# SCH_Driver_RL.net
KiCad netlist of a schematic drawn in Altium Designer
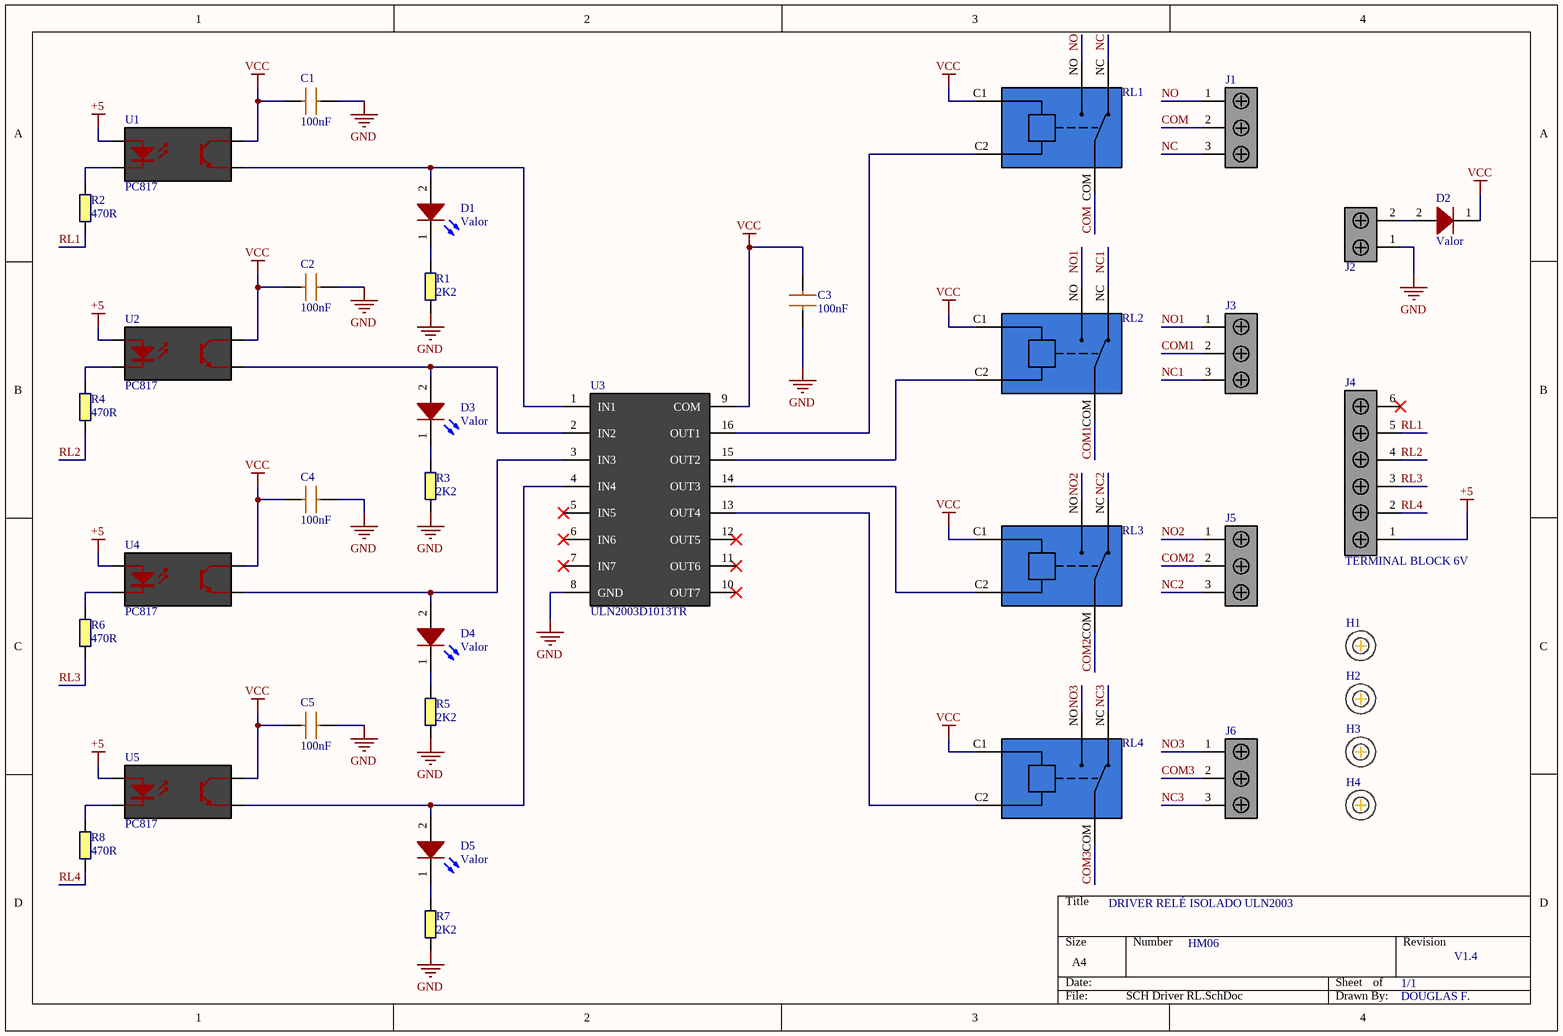
[diagram p0: SCH Driver RL.SchDoc]

(export (version "E")
  (design (tool "Eeschema 10.0.6"))
  (components
    (comp (ref "C1")
      (value "100nF")
      (footprint "RAD-0.2")
      (description "Capacitor")
      (fields (field (name "PUBLISHER") "Altium Limited"))
      (libsource (lib "Driver relé") (part "CAPACITOR"))
    )
    (comp (ref "C2")
      (value "100nF")
      (footprint "RAD-0.2")
      (description "Capacitor")
      (fields (field (name "PUBLISHER") "Altium Limited"))
      (libsource (lib "Driver relé") (part "CAPACITOR"))
    )
    (comp (ref "C3")
      (value "100nF")
      (footprint "RAD-0.2")
      (description "Capacitor")
      (fields (field (name "PUBLISHER") "Altium Limited"))
      (libsource (lib "Driver relé") (part "CAPACITOR"))
    )
    (comp (ref "C4")
      (value "100nF")
      (footprint "RAD-0.2")
      (description "Capacitor")
      (fields (field (name "PUBLISHER") "Altium Limited"))
      (libsource (lib "Driver relé") (part "CAPACITOR"))
    )
    (comp (ref "C5")
      (value "100nF")
      (footprint "RAD-0.2")
      (description "Capacitor")
      (fields (field (name "PUBLISHER") "Altium Limited"))
      (libsource (lib "Driver relé") (part "CAPACITOR"))
    )
    (comp (ref "D1")
      (value "Valor")
      (footprint "LED 3MM")
      (description "Typical RED, GREEN, YELLOW, AMBER GaAs LED")
      (fields (field (name "PUBLISHER") "Altium Limited"))
      (libsource (lib "Driver relé") (part "LED"))
    )
    (comp (ref "D2")
      (value "Valor")
      (footprint "1N4007 DO-41")
      (description "Diodo rapido")
      (fields (field (name "PUBLISHER") "Altium Limited"))
      (libsource (lib "Driver relé") (part "DIODO 1N4007"))
    )
    (comp (ref "D3")
      (value "Valor")
      (footprint "LED 3MM")
      (description "Typical RED, GREEN, YELLOW, AMBER GaAs LED")
      (fields (field (name "PUBLISHER") "Altium Limited"))
      (libsource (lib "Driver relé") (part "LED"))
    )
    (comp (ref "D4")
      (value "Valor")
      (footprint "LED 3MM")
      (description "Typical RED, GREEN, YELLOW, AMBER GaAs LED")
      (fields (field (name "PUBLISHER") "Altium Limited"))
      (libsource (lib "Driver relé") (part "LED"))
    )
    (comp (ref "D5")
      (value "Valor")
      (footprint "LED 3MM")
      (description "Typical RED, GREEN, YELLOW, AMBER GaAs LED")
      (fields (field (name "PUBLISHER") "Altium Limited"))
      (libsource (lib "Driver relé") (part "LED"))
    )
    (comp (ref "H1") (value "M3") (footprint "Parafuso M3") (libsource (lib "Driver relé") (part "Furo M3")))
    (comp (ref "H2") (value "M3") (footprint "Parafuso M3") (libsource (lib "Driver relé") (part "Furo M3")))
    (comp (ref "H3") (value "M3") (footprint "Parafuso M3") (libsource (lib "Driver relé") (part "Furo M3")))
    (comp (ref "H4") (value "M3") (footprint "Parafuso M3") (libsource (lib "Driver relé") (part "Furo M3")))
    (comp (ref "J1")
      (value "Conector 2v Phoenix")
      (footprint "Terminal block 5mm 3V")
      (description "Block, Terminal; 6 A; 63 V; 5 mm; 26 to 20 AWG; 3; Screw; Soldering; 1.5 kV")
      (fields
        (field (name "MANUFACTURER") "Phoenix Contact")
        (field (name "MANUFACTURER PART NUMBER") "1725656")
      )
      (libsource (lib "Driver relé") (part "TERMINAL BLOCK 3V"))
    )
    (comp (ref "J2")
      (value "Conector 2v Phoenix")
      (footprint "Terminal block 5mm 2V")
      (description "Block, Terminal; 6 A; 63 V; 5 mm; 26 to 20 AWG; 2; Screw; Soldering; 1.5 kV")
      (fields
        (field (name "MANUFACTURER") "Phoenix Contact")
        (field (name "MANUFACTURER PART NUMBER") "1725656")
      )
      (libsource (lib "Driver relé") (part "TERMINAL BLOCK 2V"))
    )
    (comp (ref "J3")
      (value "Conector 2v Phoenix")
      (footprint "Terminal block 5mm 3V")
      (description "Block, Terminal; 6 A; 63 V; 5 mm; 26 to 20 AWG; 3; Screw; Soldering; 1.5 kV")
      (fields
        (field (name "MANUFACTURER") "Phoenix Contact")
        (field (name "MANUFACTURER PART NUMBER") "1725656")
      )
      (libsource (lib "Driver relé") (part "TERMINAL BLOCK 3V"))
    )
    (comp (ref "J4")
      (value "TERMINAL BLOCK 6V")
      (footprint "Terminal block 5mm 6V")
      (description "Block, Terminal; 6 A; 63 V; 5 mm; 26 to 20 AWG; 6 Screw; Soldering; 1.5 kV")
      (libsource (lib "Driver relé") (part "TERMINAL BLOCK 6V"))
    )
    (comp (ref "J5")
      (value "Conector 2v Phoenix")
      (footprint "Terminal block 5mm 3V")
      (description "Block, Terminal; 6 A; 63 V; 5 mm; 26 to 20 AWG; 3; Screw; Soldering; 1.5 kV")
      (fields
        (field (name "MANUFACTURER") "Phoenix Contact")
        (field (name "MANUFACTURER PART NUMBER") "1725656")
      )
      (libsource (lib "Driver relé") (part "TERMINAL BLOCK 3V"))
    )
    (comp (ref "J6")
      (value "Conector 2v Phoenix")
      (footprint "Terminal block 5mm 3V")
      (description "Block, Terminal; 6 A; 63 V; 5 mm; 26 to 20 AWG; 3; Screw; Soldering; 1.5 kV")
      (fields
        (field (name "MANUFACTURER") "Phoenix Contact")
        (field (name "MANUFACTURER PART NUMBER") "1725656")
      )
      (libsource (lib "Driver relé") (part "TERMINAL BLOCK 3V"))
    )
    (comp (ref "R1")
      (value "2K2")
      (footprint "RES 1/4 PTH")
      (description "Resistor")
      (fields (field (name "PUBLISHER") "Altium Limited"))
      (libsource (lib "") (part "RESISTOR 1/4W_1"))
    )
    (comp (ref "R2")
      (value "470R")
      (footprint "RES 1/4 PTH")
      (description "Resistor")
      (fields (field (name "PUBLISHER") "Altium Limited"))
      (libsource (lib "Driver relé") (part "RESISTOR 1/4W"))
    )
    (comp (ref "R3")
      (value "2K2")
      (footprint "RES 1/4 PTH")
      (description "Resistor")
      (fields (field (name "PUBLISHER") "Altium Limited"))
      (libsource (lib "") (part "RESISTOR 1/4W_1"))
    )
    (comp (ref "R4")
      (value "470R")
      (footprint "RES 1/4 PTH")
      (description "Resistor")
      (fields (field (name "PUBLISHER") "Altium Limited"))
      (libsource (lib "Driver relé") (part "RESISTOR 1/4W"))
    )
    (comp (ref "R5")
      (value "2K2")
      (footprint "RES 1/4 PTH")
      (description "Resistor")
      (fields (field (name "PUBLISHER") "Altium Limited"))
      (libsource (lib "") (part "RESISTOR 1/4W_1"))
    )
    (comp (ref "R6")
      (value "470R")
      (footprint "RES 1/4 PTH")
      (description "Resistor")
      (fields (field (name "PUBLISHER") "Altium Limited"))
      (libsource (lib "Driver relé") (part "RESISTOR 1/4W"))
    )
    (comp (ref "R7")
      (value "2K2")
      (footprint "RES 1/4 PTH")
      (description "Resistor")
      (fields (field (name "PUBLISHER") "Altium Limited"))
      (libsource (lib "") (part "RESISTOR 1/4W_1"))
    )
    (comp (ref "R8")
      (value "470R")
      (footprint "RES 1/4 PTH")
      (description "Resistor")
      (fields (field (name "PUBLISHER") "Altium Limited"))
      (libsource (lib "Driver relé") (part "RESISTOR 1/4W"))
    )
    (comp (ref "RL1")
      (value "Relé 12v 5p")
      (footprint "RELAY")
      (libsource (lib "Driver relé") (part "Relé 12v 5p"))
    )
    (comp (ref "RL2")
      (value "Relé 12v 5p")
      (footprint "RELAY")
      (libsource (lib "Driver relé") (part "Relé 12v 5p"))
    )
    (comp (ref "RL3")
      (value "Relé 12v 5p")
      (footprint "RELAY")
      (libsource (lib "Driver relé") (part "Relé 12v 5p"))
    )
    (comp (ref "RL4")
      (value "Relé 12v 5p")
      (footprint "RELAY")
      (libsource (lib "Driver relé") (part "Relé 12v 5p"))
    )
    (comp (ref "U1") (value "PC817") (footprint "PC817 DIP-4") (libsource (lib "Driver relé") (part "PC817")))
    (comp (ref "U2") (value "PC817") (footprint "PC817 DIP-4") (libsource (lib "Driver relé") (part "PC817")))
    (comp (ref "U3")
      (value "ULN2003D1013TR")
      (footprint "PDIP-16")
      (description "ULN Series 50V 500 mA High Voltage High Current Seven Darlington Array - SOIC-16")
      (fields (field (name "MANUFACTURER") "STMicroelectronics"))
      (libsource (lib "Driver relé") (part "ULN2003D1013TR"))
    )
    (comp (ref "U4") (value "PC817") (footprint "PC817 DIP-4") (libsource (lib "Driver relé") (part "PC817")))
    (comp (ref "U5") (value "PC817") (footprint "PC817 DIP-4") (libsource (lib "Driver relé") (part "PC817")))
  )
  (nets
    (net (code "1") (name "+5") (class "Default")
      (node (ref "J4") (pin "1") (pinfunction "1_1") (pintype "passive"))
      (node (ref "U1") (pin "1") (pinfunction "A_1") (pintype "passive"))
      (node (ref "U2") (pin "1") (pinfunction "A_1") (pintype "passive"))
      (node (ref "U4") (pin "1") (pinfunction "A_1") (pintype "passive"))
      (node (ref "U5") (pin "1") (pinfunction "A_1") (pintype "passive"))
    )
    (net (code "2") (name "/COM") (class "Default")
      (node (ref "J1") (pin "2") (pinfunction "2_2") (pintype "passive"))
      (node (ref "RL1") (pin "COM") (pinfunction "COM_COM") (pintype "passive"))
    )
    (net (code "3") (name "/COM1") (class "Default")
      (node (ref "J3") (pin "2") (pinfunction "2_2") (pintype "passive"))
      (node (ref "RL2") (pin "COM") (pinfunction "COM_COM") (pintype "passive"))
    )
    (net (code "4") (name "/COM2") (class "Default")
      (node (ref "J5") (pin "2") (pinfunction "2_2") (pintype "passive"))
      (node (ref "RL3") (pin "COM") (pinfunction "COM_COM") (pintype "passive"))
    )
    (net (code "5") (name "/COM3") (class "Default")
      (node (ref "J6") (pin "2") (pinfunction "2_2") (pintype "passive"))
      (node (ref "RL4") (pin "COM") (pinfunction "COM_COM") (pintype "passive"))
    )
    (net (code "6") (name "/NC") (class "Default")
      (node (ref "J1") (pin "3") (pinfunction "3_3") (pintype "passive"))
      (node (ref "RL1") (pin "NC") (pinfunction "NC_NC") (pintype "passive"))
    )
    (net (code "7") (name "/NC1") (class "Default")
      (node (ref "J3") (pin "3") (pinfunction "3_3") (pintype "passive"))
      (node (ref "RL2") (pin "NC") (pinfunction "NC_NC") (pintype "passive"))
    )
    (net (code "8") (name "/NC2") (class "Default")
      (node (ref "J5") (pin "3") (pinfunction "3_3") (pintype "passive"))
      (node (ref "RL3") (pin "NC") (pinfunction "NC_NC") (pintype "passive"))
    )
    (net (code "9") (name "/NC3") (class "Default")
      (node (ref "J6") (pin "3") (pinfunction "3_3") (pintype "passive"))
      (node (ref "RL4") (pin "NC") (pinfunction "NC_NC") (pintype "passive"))
    )
    (net (code "10") (name "/NO") (class "Default")
      (node (ref "J1") (pin "1") (pinfunction "1_1") (pintype "passive"))
      (node (ref "RL1") (pin "NO") (pinfunction "NO_NO") (pintype "passive"))
    )
    (net (code "11") (name "/NO1") (class "Default")
      (node (ref "J3") (pin "1") (pinfunction "1_1") (pintype "passive"))
      (node (ref "RL2") (pin "NO") (pinfunction "NO_NO") (pintype "passive"))
    )
    (net (code "12") (name "/NO2") (class "Default")
      (node (ref "J5") (pin "1") (pinfunction "1_1") (pintype "passive"))
      (node (ref "RL3") (pin "NO") (pinfunction "NO_NO") (pintype "passive"))
    )
    (net (code "13") (name "/NO3") (class "Default")
      (node (ref "J6") (pin "1") (pinfunction "1_1") (pintype "passive"))
      (node (ref "RL4") (pin "NO") (pinfunction "NO_NO") (pintype "passive"))
    )
    (net (code "14") (name "/RL1") (class "Default")
      (node (ref "J4") (pin "5") (pinfunction "5_5") (pintype "passive"))
      (node (ref "R2") (pin "1") (pinfunction "1_1") (pintype "passive"))
    )
    (net (code "15") (name "/RL2") (class "Default")
      (node (ref "J4") (pin "4") (pinfunction "4_4") (pintype "passive"))
      (node (ref "R4") (pin "1") (pinfunction "1_1") (pintype "passive"))
    )
    (net (code "16") (name "/RL3") (class "Default")
      (node (ref "J4") (pin "3") (pinfunction "3_3") (pintype "passive"))
      (node (ref "R6") (pin "1") (pinfunction "1_1") (pintype "passive"))
    )
    (net (code "17") (name "/RL4") (class "Default")
      (node (ref "J4") (pin "2") (pinfunction "2_2") (pintype "passive"))
      (node (ref "R8") (pin "1") (pinfunction "1_1") (pintype "passive"))
    )
    (net (code "18") (name "GND") (class "Default")
      (node (ref "C1") (pin "1") (pinfunction "1_1") (pintype "passive"))
      (node (ref "C2") (pin "1") (pinfunction "1_1") (pintype "passive"))
      (node (ref "C3") (pin "1") (pinfunction "1_1") (pintype "passive"))
      (node (ref "C4") (pin "1") (pinfunction "1_1") (pintype "passive"))
      (node (ref "C5") (pin "1") (pinfunction "1_1") (pintype "passive"))
      (node (ref "J2") (pin "1") (pinfunction "1_1") (pintype "passive"))
      (node (ref "R1") (pin "2") (pinfunction "2_2") (pintype "passive"))
      (node (ref "R3") (pin "2") (pinfunction "2_2") (pintype "passive"))
      (node (ref "R5") (pin "2") (pinfunction "2_2") (pintype "passive"))
      (node (ref "R7") (pin "2") (pinfunction "2_2") (pintype "passive"))
      (node (ref "U3") (pin "8") (pinfunction "GND_8") (pintype "passive"))
    )
    (net (code "19") (name "Net-(D1-1)") (class "Default")
      (node (ref "D1") (pin "2") (pinfunction "1_2") (pintype "passive"))
      (node (ref "U1") (pin "3") (pinfunction "E_3") (pintype "passive"))
      (node (ref "U3") (pin "1") (pinfunction "IN1_1") (pintype "passive"))
    )
    (net (code "20") (name "Net-(D1-2)") (class "Default")
      (node (ref "D1") (pin "1") (pinfunction "2_1") (pintype "passive"))
      (node (ref "R1") (pin "1") (pinfunction "1_1") (pintype "passive"))
    )
    (net (code "21") (name "Net-(D2-Pad2)") (class "Default")
      (node (ref "D2") (pin "2") (pinfunction "2_2") (pintype "passive"))
      (node (ref "J2") (pin "2") (pinfunction "2_2") (pintype "passive"))
    )
    (net (code "22") (name "Net-(D3-1)") (class "Default")
      (node (ref "D3") (pin "2") (pinfunction "1_2") (pintype "passive"))
      (node (ref "U2") (pin "3") (pinfunction "E_3") (pintype "passive"))
      (node (ref "U3") (pin "2") (pinfunction "IN2_2") (pintype "passive"))
    )
    (net (code "23") (name "Net-(D3-2)") (class "Default")
      (node (ref "D3") (pin "1") (pinfunction "2_1") (pintype "passive"))
      (node (ref "R3") (pin "1") (pinfunction "1_1") (pintype "passive"))
    )
    (net (code "24") (name "Net-(D4-1)") (class "Default")
      (node (ref "D4") (pin "2") (pinfunction "1_2") (pintype "passive"))
      (node (ref "U3") (pin "3") (pinfunction "IN3_3") (pintype "passive"))
      (node (ref "U4") (pin "3") (pinfunction "E_3") (pintype "passive"))
    )
    (net (code "25") (name "Net-(D4-2)") (class "Default")
      (node (ref "D4") (pin "1") (pinfunction "2_1") (pintype "passive"))
      (node (ref "R5") (pin "1") (pinfunction "1_1") (pintype "passive"))
    )
    (net (code "26") (name "Net-(D5-1)") (class "Default")
      (node (ref "D5") (pin "2") (pinfunction "1_2") (pintype "passive"))
      (node (ref "U3") (pin "4") (pinfunction "IN4_4") (pintype "passive"))
      (node (ref "U5") (pin "3") (pinfunction "E_3") (pintype "passive"))
    )
    (net (code "27") (name "Net-(D5-2)") (class "Default")
      (node (ref "D5") (pin "1") (pinfunction "2_1") (pintype "passive"))
      (node (ref "R7") (pin "1") (pinfunction "1_1") (pintype "passive"))
    )
    (net (code "28") (name "Net-(RL1-COIL_2)") (class "Default")
      (node (ref "RL1") (pin "C2") (pinfunction "COIL_2_C2") (pintype "passive"))
      (node (ref "U3") (pin "16") (pinfunction "OUT1_16") (pintype "passive"))
    )
    (net (code "29") (name "Net-(RL2-COIL_2)") (class "Default")
      (node (ref "RL2") (pin "C2") (pinfunction "COIL_2_C2") (pintype "passive"))
      (node (ref "U3") (pin "15") (pinfunction "OUT2_15") (pintype "passive"))
    )
    (net (code "30") (name "Net-(RL3-COIL_2)") (class "Default")
      (node (ref "RL3") (pin "C2") (pinfunction "COIL_2_C2") (pintype "passive"))
      (node (ref "U3") (pin "14") (pinfunction "OUT3_14") (pintype "passive"))
    )
    (net (code "31") (name "Net-(RL4-COIL_2)") (class "Default")
      (node (ref "RL4") (pin "C2") (pinfunction "COIL_2_C2") (pintype "passive"))
      (node (ref "U3") (pin "13") (pinfunction "OUT4_13") (pintype "passive"))
    )
    (net (code "32") (name "Net-(U1-K)") (class "Default")
      (node (ref "R2") (pin "2") (pinfunction "2_2") (pintype "passive"))
      (node (ref "U1") (pin "2") (pinfunction "K_2") (pintype "passive"))
    )
    (net (code "33") (name "Net-(U2-K)") (class "Default")
      (node (ref "R4") (pin "2") (pinfunction "2_2") (pintype "passive"))
      (node (ref "U2") (pin "2") (pinfunction "K_2") (pintype "passive"))
    )
    (net (code "34") (name "Net-(U4-K)") (class "Default")
      (node (ref "R6") (pin "2") (pinfunction "2_2") (pintype "passive"))
      (node (ref "U4") (pin "2") (pinfunction "K_2") (pintype "passive"))
    )
    (net (code "35") (name "Net-(U5-K)") (class "Default")
      (node (ref "R8") (pin "2") (pinfunction "2_2") (pintype "passive"))
      (node (ref "U5") (pin "2") (pinfunction "K_2") (pintype "passive"))
    )
    (net (code "36") (name "VCC") (class "Default")
      (node (ref "C1") (pin "2") (pinfunction "2_2") (pintype "passive"))
      (node (ref "C2") (pin "2") (pinfunction "2_2") (pintype "passive"))
      (node (ref "C3") (pin "2") (pinfunction "2_2") (pintype "passive"))
      (node (ref "C4") (pin "2") (pinfunction "2_2") (pintype "passive"))
      (node (ref "C5") (pin "2") (pinfunction "2_2") (pintype "passive"))
      (node (ref "D2") (pin "1") (pinfunction "1_1") (pintype "passive"))
      (node (ref "RL1") (pin "C1") (pinfunction "COIL_1_C1") (pintype "passive"))
      (node (ref "RL2") (pin "C1") (pinfunction "COIL_1_C1") (pintype "passive"))
      (node (ref "RL3") (pin "C1") (pinfunction "COIL_1_C1") (pintype "passive"))
      (node (ref "RL4") (pin "C1") (pinfunction "COIL_1_C1") (pintype "passive"))
      (node (ref "U1") (pin "4") (pinfunction "C_4") (pintype "passive"))
      (node (ref "U2") (pin "4") (pinfunction "C_4") (pintype "passive"))
      (node (ref "U3") (pin "9") (pinfunction "COM_9") (pintype "passive"))
      (node (ref "U4") (pin "4") (pinfunction "C_4") (pintype "passive"))
      (node (ref "U5") (pin "4") (pinfunction "C_4") (pintype "passive"))
    )
    (net (code "37") (name "unconnected-(J4-Pad6)") (class "Default")
      (node (ref "J4") (pin "6") (pinfunction "6_6") (pintype "passive+no_connect"))
    )
    (net (code "38") (name "unconnected-(U3-IN5-Pad5)") (class "Default")
      (node (ref "U3") (pin "5") (pinfunction "IN5_5") (pintype "passive+no_connect"))
    )
    (net (code "39") (name "unconnected-(U3-IN6-Pad6)") (class "Default")
      (node (ref "U3") (pin "6") (pinfunction "IN6_6") (pintype "passive+no_connect"))
    )
    (net (code "40") (name "unconnected-(U3-IN7-Pad7)") (class "Default")
      (node (ref "U3") (pin "7") (pinfunction "IN7_7") (pintype "passive+no_connect"))
    )
    (net (code "41") (name "unconnected-(U3-OUT5-Pad12)") (class "Default")
      (node (ref "U3") (pin "12") (pinfunction "OUT5_12") (pintype "passive+no_connect"))
    )
    (net (code "42") (name "unconnected-(U3-OUT6-Pad11)") (class "Default")
      (node (ref "U3") (pin "11") (pinfunction "OUT6_11") (pintype "passive+no_connect"))
    )
    (net (code "43") (name "unconnected-(U3-OUT7-Pad10)") (class "Default")
      (node (ref "U3") (pin "10") (pinfunction "OUT7_10") (pintype "passive+no_connect"))
    )
  )
)
